# uControl_v1.net
KiCad netlist of a schematic drawn in EAGLE
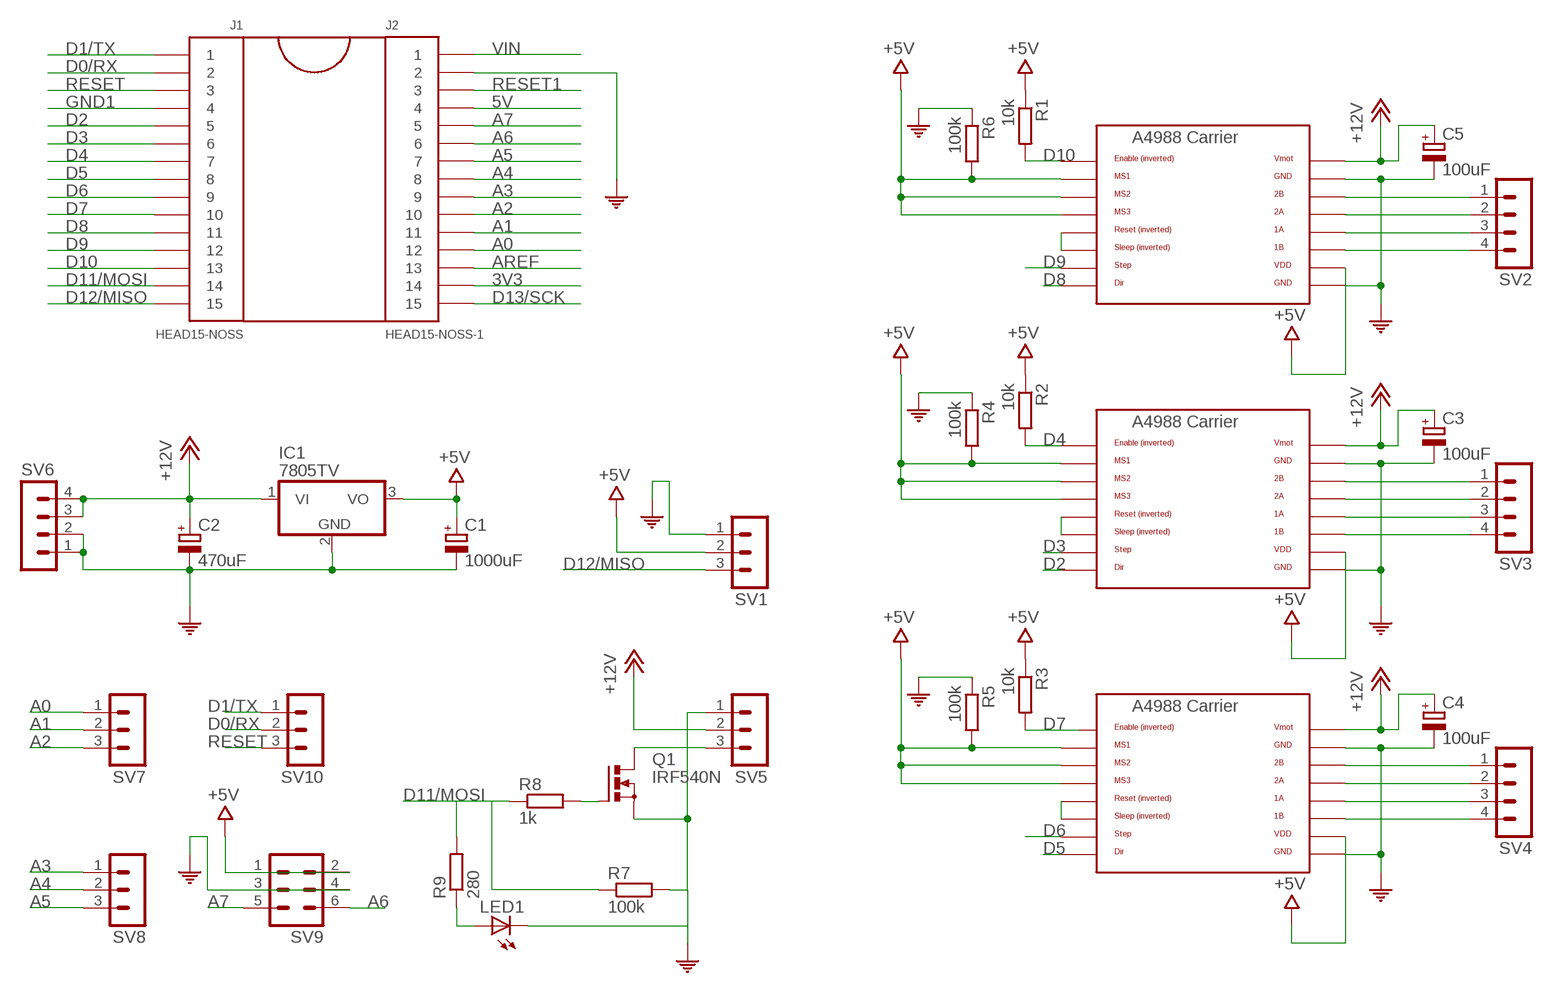
[diagram p0: schematic, sheet 1]

(export (version "E")
  (design (tool "Eeschema 10.0.6"))
  (components
    (comp (ref "C1")
      (value "1000uF")
      (footprint "eagle-import:TAP5-70")
      (libsource (lib "eagle-import") (part "CPOL-EUTAP5-70"))
    )
    (comp (ref "C2")
      (value "470uF")
      (footprint "eagle-import:TAP5-70")
      (libsource (lib "eagle-import") (part "CPOL-EUTAP5-70"))
    )
    (comp (ref "C3")
      (value "100uF")
      (footprint "eagle-import:TAP5-70")
      (libsource (lib "eagle-import") (part "CPOL-EUTAP5-70"))
    )
    (comp (ref "C4")
      (value "100uF")
      (footprint "eagle-import:TAP5-70")
      (libsource (lib "eagle-import") (part "CPOL-EUTAP5-70"))
    )
    (comp (ref "C5")
      (value "100uF")
      (footprint "eagle-import:TAP5-70")
      (libsource (lib "eagle-import") (part "CPOL-EUTAP5-70"))
    )
    (comp (ref "IC1")
      (value "7805TV")
      (footprint "eagle-import:TO220V")
      (libsource (lib "eagle-import") (part "78TV05"))
    )
    (comp (ref "J1")
      (value "HEAD15-NOSS")
      (footprint "eagle-import:HEAD15-NOSS")
      (libsource (lib "eagle-import") (part "HEAD15-NOSS"))
    )
    (comp (ref "J2")
      (value "HEAD15-NOSS-1")
      (footprint "eagle-import:HEAD15-NOSS-1")
      (libsource (lib "eagle-import") (part "HEAD15-NOSS-1"))
    )
    (comp (ref "LED1")
      (value "LED3MM")
      (footprint "eagle-import:LED3MM")
      (libsource (lib "eagle-import") (part "LED3MM"))
    )
    (comp (ref "Q1")
      (value "IRF540N")
      (footprint "eagle-import:TO220BV")
      (libsource (lib "eagle-import") (part "PMOSFET_NTO220BV"))
    )
    (comp (ref "R1")
      (value "10k")
      (footprint "eagle-import:0207_10")
      (libsource (lib "eagle-import") (part "R-EU_0207/10"))
    )
    (comp (ref "R2")
      (value "10k")
      (footprint "eagle-import:0207_10")
      (libsource (lib "eagle-import") (part "R-EU_0207/10"))
    )
    (comp (ref "R3")
      (value "10k")
      (footprint "eagle-import:0207_10")
      (libsource (lib "eagle-import") (part "R-EU_0207/10"))
    )
    (comp (ref "R4")
      (value "100k")
      (footprint "eagle-import:0207_10")
      (libsource (lib "eagle-import") (part "R-EU_0207/10"))
    )
    (comp (ref "R5")
      (value "100k")
      (footprint "eagle-import:0207_10")
      (libsource (lib "eagle-import") (part "R-EU_0207/10"))
    )
    (comp (ref "R6")
      (value "100k")
      (footprint "eagle-import:0207_10")
      (libsource (lib "eagle-import") (part "R-EU_0207/10"))
    )
    (comp (ref "R7")
      (value "100k")
      (footprint "eagle-import:0207_10")
      (libsource (lib "eagle-import") (part "R-EU_0207/10"))
    )
    (comp (ref "R8")
      (value "1k")
      (footprint "eagle-import:0207_10")
      (libsource (lib "eagle-import") (part "R-EU_0207/10"))
    )
    (comp (ref "R9")
      (value "280")
      (footprint "eagle-import:0207_10")
      (libsource (lib "eagle-import") (part "R-EU_0207/10"))
    )
    (comp (ref "SV1")
      (value "MA03-1")
      (footprint "eagle-import:MA03-1")
      (libsource (lib "eagle-import") (part "MA03-1"))
    )
    (comp (ref "SV2")
      (value "MA04-1")
      (footprint "eagle-import:MA04-1")
      (libsource (lib "eagle-import") (part "MA04-1"))
    )
    (comp (ref "SV3")
      (value "MA04-1")
      (footprint "eagle-import:MA04-1")
      (libsource (lib "eagle-import") (part "MA04-1"))
    )
    (comp (ref "SV4")
      (value "MA04-1")
      (footprint "eagle-import:MA04-1")
      (libsource (lib "eagle-import") (part "MA04-1"))
    )
    (comp (ref "SV5")
      (value "MA03-1")
      (footprint "eagle-import:MA03-1")
      (libsource (lib "eagle-import") (part "MA03-1"))
    )
    (comp (ref "SV6")
      (value "MA04-1")
      (footprint "eagle-import:MA04-1")
      (libsource (lib "eagle-import") (part "MA04-1"))
    )
    (comp (ref "SV7")
      (value "MA03-1")
      (footprint "eagle-import:MA03-1")
      (libsource (lib "eagle-import") (part "MA03-1"))
    )
    (comp (ref "SV8")
      (value "MA03-1")
      (footprint "eagle-import:MA03-1")
      (libsource (lib "eagle-import") (part "MA03-1"))
    )
    (comp (ref "SV9")
      (value "MA03-2")
      (footprint "eagle-import:MA03-2")
      (libsource (lib "eagle-import") (part "MA03-2"))
    )
    (comp (ref "SV10")
      (value "MA03-1")
      (footprint "eagle-import:MA03-1")
      (libsource (lib "eagle-import") (part "MA03-1"))
    )
    (comp (ref "U$3")
      (value "POLOLU_A4983CARRIER")
      (footprint "eagle-import:A4988BREAKOUT")
      (libsource (lib "eagle-import") (part "POLOLU_A4983CARRIER"))
    )
    (comp (ref "U$4")
      (value "A4988BREAKOUT")
      (footprint "eagle-import:A4988BREAKOUT")
      (libsource (lib "eagle-import") (part "A4988BREAKOUT"))
    )
    (comp (ref "U$5")
      (value "A4988BREAKOUT")
      (footprint "eagle-import:A4988BREAKOUT")
      (libsource (lib "eagle-import") (part "A4988BREAKOUT"))
    )
  )
  (nets
    (net (code "1") (name "+5V") (class "Default")
      (node (ref "C1") (pin "+") (pinfunction "+_+") (pintype "passive"))
      (node (ref "IC1") (pin "3") (pinfunction "VO_3") (pintype "passive"))
      (node (ref "R1") (pin "1") (pinfunction "1_1") (pintype "passive"))
      (node (ref "R2") (pin "1") (pinfunction "1_1") (pintype "passive"))
      (node (ref "R3") (pin "1") (pinfunction "1_1") (pintype "passive"))
      (node (ref "R4") (pin "2") (pinfunction "2_2") (pintype "passive"))
      (node (ref "R5") (pin "2") (pinfunction "2_2") (pintype "passive"))
      (node (ref "R6") (pin "2") (pinfunction "2_2") (pintype "passive"))
      (node (ref "SV1") (pin "2") (pinfunction "2_2") (pintype "passive"))
      (node (ref "SV9") (pin "1") (pinfunction "1_1") (pintype "passive"))
      (node (ref "SV9") (pin "2") (pinfunction "2_2") (pintype "passive"))
      (node (ref "U$3") (pin "MS1") (pinfunction "MS1_MS1") (pintype "input"))
      (node (ref "U$3") (pin "MS2") (pinfunction "MS2_MS2") (pintype "input"))
      (node (ref "U$3") (pin "MS3") (pinfunction "MS3_MS3") (pintype "input"))
      (node (ref "U$3") (pin "VDD") (pinfunction "VDD_VDD") (pintype "power_in"))
      (node (ref "U$4") (pin "MS1") (pinfunction "MS1_MS1") (pintype "input"))
      (node (ref "U$4") (pin "MS2") (pinfunction "MS2_MS2") (pintype "input"))
      (node (ref "U$4") (pin "MS3") (pinfunction "MS3_MS3") (pintype "input"))
      (node (ref "U$4") (pin "VDD") (pinfunction "VDD_VDD") (pintype "power_in"))
      (node (ref "U$5") (pin "MS1") (pinfunction "MS1_MS1") (pintype "input"))
      (node (ref "U$5") (pin "MS2") (pinfunction "MS2_MS2") (pintype "input"))
      (node (ref "U$5") (pin "MS3") (pinfunction "MS3_MS3") (pintype "input"))
      (node (ref "U$5") (pin "VDD") (pinfunction "VDD_VDD") (pintype "power_in"))
    )
    (net (code "2") (name "+12V") (class "Default")
      (node (ref "C2") (pin "+") (pinfunction "+_+") (pintype "passive"))
      (node (ref "C3") (pin "+") (pinfunction "+_+") (pintype "passive"))
      (node (ref "C4") (pin "+") (pinfunction "+_+") (pintype "passive"))
      (node (ref "C5") (pin "+") (pinfunction "+_+") (pintype "passive"))
      (node (ref "IC1") (pin "1") (pinfunction "VI_1") (pintype "input"))
      (node (ref "SV5") (pin "2") (pinfunction "2_2") (pintype "passive"))
      (node (ref "SV6") (pin "3") (pinfunction "3_3") (pintype "passive"))
      (node (ref "SV6") (pin "4") (pinfunction "4_4") (pintype "passive"))
      (node (ref "U$3") (pin "VMOT") (pinfunction "VMOT_VMOT") (pintype "power_in"))
      (node (ref "U$4") (pin "VMOT") (pinfunction "VMOT_VMOT") (pintype "power_in"))
      (node (ref "U$5") (pin "VMOT") (pinfunction "VMOT_VMOT") (pintype "power_in"))
    )
    (net (code "3") (name "/3V3") (class "Default")
      (node (ref "J2") (pin "14") (pinfunction "14_14") (pintype "passive"))
    )
    (net (code "4") (name "/5V") (class "Default")
      (node (ref "J2") (pin "4") (pinfunction "4_4") (pintype "passive"))
    )
    (net (code "5") (name "/A0") (class "Default")
      (node (ref "J2") (pin "12") (pinfunction "12_12") (pintype "passive"))
      (node (ref "SV7") (pin "1") (pinfunction "1_1") (pintype "passive"))
    )
    (net (code "6") (name "/A1") (class "Default")
      (node (ref "J2") (pin "11") (pinfunction "11_11") (pintype "passive"))
      (node (ref "SV7") (pin "2") (pinfunction "2_2") (pintype "passive"))
    )
    (net (code "7") (name "/A2") (class "Default")
      (node (ref "J2") (pin "10") (pinfunction "10_10") (pintype "passive"))
      (node (ref "SV7") (pin "3") (pinfunction "3_3") (pintype "passive"))
    )
    (net (code "8") (name "/A3") (class "Default")
      (node (ref "J2") (pin "9") (pinfunction "9_9") (pintype "passive"))
      (node (ref "SV8") (pin "1") (pinfunction "1_1") (pintype "passive"))
    )
    (net (code "9") (name "/A4") (class "Default")
      (node (ref "J2") (pin "8") (pinfunction "8_8") (pintype "passive"))
      (node (ref "SV8") (pin "2") (pinfunction "2_2") (pintype "passive"))
    )
    (net (code "10") (name "/A5") (class "Default")
      (node (ref "J2") (pin "7") (pinfunction "7_7") (pintype "passive"))
      (node (ref "SV8") (pin "3") (pinfunction "3_3") (pintype "passive"))
    )
    (net (code "11") (name "/A6") (class "Default")
      (node (ref "J2") (pin "6") (pinfunction "6_6") (pintype "passive"))
      (node (ref "SV9") (pin "6") (pinfunction "6_6") (pintype "passive"))
    )
    (net (code "12") (name "/A7") (class "Default")
      (node (ref "J2") (pin "5") (pinfunction "5_5") (pintype "passive"))
      (node (ref "SV9") (pin "5") (pinfunction "5_5") (pintype "passive"))
    )
    (net (code "13") (name "/AREF") (class "Default")
      (node (ref "J2") (pin "13") (pinfunction "13_13") (pintype "passive"))
    )
    (net (code "14") (name "/D0{slash}RX") (class "Default")
      (node (ref "J1") (pin "2") (pinfunction "2_2") (pintype "passive"))
      (node (ref "SV10") (pin "2") (pinfunction "2_2") (pintype "passive"))
    )
    (net (code "15") (name "/D1{slash}TX") (class "Default")
      (node (ref "J1") (pin "1") (pinfunction "1_1") (pintype "passive"))
      (node (ref "SV10") (pin "1") (pinfunction "1_1") (pintype "passive"))
    )
    (net (code "16") (name "/D2") (class "Default")
      (node (ref "J1") (pin "5") (pinfunction "5_5") (pintype "passive"))
      (node (ref "U$5") (pin "DIR") (pinfunction "DIR_DIR") (pintype "input"))
    )
    (net (code "17") (name "/D3") (class "Default")
      (node (ref "J1") (pin "6") (pinfunction "6_6") (pintype "passive"))
      (node (ref "U$5") (pin "STEP") (pinfunction "STEP_STEP") (pintype "input"))
    )
    (net (code "18") (name "/D4") (class "Default")
      (node (ref "J1") (pin "7") (pinfunction "7_7") (pintype "passive"))
      (node (ref "R2") (pin "2") (pinfunction "2_2") (pintype "passive"))
      (node (ref "U$5") (pin "EN") (pinfunction "EN_EN") (pintype "input"))
    )
    (net (code "19") (name "/D5") (class "Default")
      (node (ref "J1") (pin "8") (pinfunction "8_8") (pintype "passive"))
      (node (ref "U$4") (pin "DIR") (pinfunction "DIR_DIR") (pintype "input"))
    )
    (net (code "20") (name "/D6") (class "Default")
      (node (ref "J1") (pin "9") (pinfunction "9_9") (pintype "passive"))
      (node (ref "U$4") (pin "STEP") (pinfunction "STEP_STEP") (pintype "input"))
    )
    (net (code "21") (name "/D7") (class "Default")
      (node (ref "J1") (pin "10") (pinfunction "10_10") (pintype "passive"))
      (node (ref "R3") (pin "2") (pinfunction "2_2") (pintype "passive"))
      (node (ref "U$4") (pin "EN") (pinfunction "EN_EN") (pintype "input"))
    )
    (net (code "22") (name "/D8") (class "Default")
      (node (ref "J1") (pin "11") (pinfunction "11_11") (pintype "passive"))
      (node (ref "U$3") (pin "DIR") (pinfunction "DIR_DIR") (pintype "input"))
    )
    (net (code "23") (name "/D9") (class "Default")
      (node (ref "J1") (pin "12") (pinfunction "12_12") (pintype "passive"))
      (node (ref "U$3") (pin "STEP") (pinfunction "STEP_STEP") (pintype "input"))
    )
    (net (code "24") (name "/D10") (class "Default")
      (node (ref "J1") (pin "13") (pinfunction "13_13") (pintype "passive"))
      (node (ref "R1") (pin "2") (pinfunction "2_2") (pintype "passive"))
      (node (ref "U$3") (pin "EN") (pinfunction "EN_EN") (pintype "input"))
    )
    (net (code "25") (name "/D11{slash}MOSI") (class "Default")
      (node (ref "J1") (pin "14") (pinfunction "14_14") (pintype "passive"))
      (node (ref "R7") (pin "1") (pinfunction "1_1") (pintype "passive"))
      (node (ref "R8") (pin "1") (pinfunction "1_1") (pintype "passive"))
      (node (ref "R9") (pin "2") (pinfunction "2_2") (pintype "passive"))
    )
    (net (code "26") (name "/D12{slash}MISO") (class "Default")
      (node (ref "J1") (pin "15") (pinfunction "15_15") (pintype "passive"))
      (node (ref "SV1") (pin "3") (pinfunction "3_3") (pintype "passive"))
    )
    (net (code "27") (name "/D13{slash}SCK") (class "Default")
      (node (ref "J2") (pin "15") (pinfunction "15_15") (pintype "passive"))
    )
    (net (code "28") (name "/GND1") (class "Default")
      (node (ref "J1") (pin "4") (pinfunction "4_4") (pintype "passive"))
    )
    (net (code "29") (name "/RESET") (class "Default")
      (node (ref "J1") (pin "3") (pinfunction "3_3") (pintype "passive"))
      (node (ref "SV10") (pin "3") (pinfunction "3_3") (pintype "passive"))
    )
    (net (code "30") (name "/RESET1") (class "Default")
      (node (ref "J2") (pin "3") (pinfunction "3_3") (pintype "passive"))
    )
    (net (code "31") (name "/VIN") (class "Default")
      (node (ref "J2") (pin "1") (pinfunction "1_1") (pintype "passive"))
    )
    (net (code "32") (name "COM") (class "Default")
      (node (ref "C1") (pin "-") (pinfunction "-_-") (pintype "passive"))
      (node (ref "C2") (pin "-") (pinfunction "-_-") (pintype "passive"))
      (node (ref "C3") (pin "-") (pinfunction "-_-") (pintype "passive"))
      (node (ref "C4") (pin "-") (pinfunction "-_-") (pintype "passive"))
      (node (ref "C5") (pin "-") (pinfunction "-_-") (pintype "passive"))
      (node (ref "IC1") (pin "2") (pinfunction "GND_2") (pintype "passive"))
      (node (ref "J2") (pin "2") (pinfunction "2_2") (pintype "passive"))
      (node (ref "LED1") (pin "K") (pinfunction "C_K") (pintype "passive"))
      (node (ref "Q1") (pin "S") (pinfunction "S_S") (pintype "passive"))
      (node (ref "R4") (pin "1") (pinfunction "1_1") (pintype "passive"))
      (node (ref "R5") (pin "1") (pinfunction "1_1") (pintype "passive"))
      (node (ref "R6") (pin "1") (pinfunction "1_1") (pintype "passive"))
      (node (ref "R7") (pin "2") (pinfunction "2_2") (pintype "passive"))
      (node (ref "SV1") (pin "1") (pinfunction "1_1") (pintype "passive"))
      (node (ref "SV5") (pin "1") (pinfunction "1_1") (pintype "passive"))
      (node (ref "SV6") (pin "1") (pinfunction "1_1") (pintype "passive"))
      (node (ref "SV6") (pin "2") (pinfunction "2_2") (pintype "passive"))
      (node (ref "SV9") (pin "3") (pinfunction "3_3") (pintype "passive"))
      (node (ref "SV9") (pin "4") (pinfunction "4_4") (pintype "passive"))
      (node (ref "U$3") (pin "GND") (pinfunction "GND_GND") (pintype "power_in"))
      (node (ref "U$3") (pin "GND@0") (pinfunction "GND_GND@0") (pintype "power_in"))
      (node (ref "U$4") (pin "GND") (pinfunction "GND_GND") (pintype "power_in"))
      (node (ref "U$4") (pin "GND@0") (pinfunction "GND_GND@0") (pintype "power_in"))
      (node (ref "U$5") (pin "GND") (pinfunction "GND_GND") (pintype "power_in"))
      (node (ref "U$5") (pin "GND@0") (pinfunction "GND_GND@0") (pintype "power_in"))
    )
    (net (code "33") (name "Net-(LED1-PadA)") (class "Default")
      (node (ref "LED1") (pin "A") (pinfunction "A_A") (pintype "passive"))
      (node (ref "R9") (pin "1") (pinfunction "1_1") (pintype "passive"))
    )
    (net (code "34") (name "Net-(Q1-PadD)") (class "Default")
      (node (ref "Q1") (pin "D") (pinfunction "D_D") (pintype "passive"))
      (node (ref "SV5") (pin "3") (pinfunction "3_3") (pintype "passive"))
    )
    (net (code "35") (name "Net-(Q1-PadG)") (class "Default")
      (node (ref "Q1") (pin "G") (pinfunction "G_G") (pintype "passive"))
      (node (ref "R8") (pin "2") (pinfunction "2_2") (pintype "passive"))
    )
    (net (code "36") (name "Net-(SV2-Pad1)") (class "Default")
      (node (ref "SV2") (pin "1") (pinfunction "1_1") (pintype "passive"))
      (node (ref "U$3") (pin "2B") (pinfunction "2B_2B") (pintype "output"))
    )
    (net (code "37") (name "Net-(SV2-Pad2)") (class "Default")
      (node (ref "SV2") (pin "2") (pinfunction "2_2") (pintype "passive"))
      (node (ref "U$3") (pin "2A") (pinfunction "2A_2A") (pintype "output"))
    )
    (net (code "38") (name "Net-(SV2-Pad3)") (class "Default")
      (node (ref "SV2") (pin "3") (pinfunction "3_3") (pintype "passive"))
      (node (ref "U$3") (pin "1A") (pinfunction "1A_1A") (pintype "output"))
    )
    (net (code "39") (name "Net-(SV2-Pad4)") (class "Default")
      (node (ref "SV2") (pin "4") (pinfunction "4_4") (pintype "passive"))
      (node (ref "U$3") (pin "1B") (pinfunction "1B_1B") (pintype "output"))
    )
    (net (code "40") (name "Net-(SV3-Pad1)") (class "Default")
      (node (ref "SV3") (pin "1") (pinfunction "1_1") (pintype "passive"))
      (node (ref "U$5") (pin "2B") (pinfunction "2B_2B") (pintype "output"))
    )
    (net (code "41") (name "Net-(SV3-Pad2)") (class "Default")
      (node (ref "SV3") (pin "2") (pinfunction "2_2") (pintype "passive"))
      (node (ref "U$5") (pin "2A") (pinfunction "2A_2A") (pintype "output"))
    )
    (net (code "42") (name "Net-(SV3-Pad3)") (class "Default")
      (node (ref "SV3") (pin "3") (pinfunction "3_3") (pintype "passive"))
      (node (ref "U$5") (pin "1A") (pinfunction "1A_1A") (pintype "output"))
    )
    (net (code "43") (name "Net-(SV3-Pad4)") (class "Default")
      (node (ref "SV3") (pin "4") (pinfunction "4_4") (pintype "passive"))
      (node (ref "U$5") (pin "1B") (pinfunction "1B_1B") (pintype "output"))
    )
    (net (code "44") (name "Net-(SV4-Pad1)") (class "Default")
      (node (ref "SV4") (pin "1") (pinfunction "1_1") (pintype "passive"))
      (node (ref "U$4") (pin "2B") (pinfunction "2B_2B") (pintype "output"))
    )
    (net (code "45") (name "Net-(SV4-Pad2)") (class "Default")
      (node (ref "SV4") (pin "2") (pinfunction "2_2") (pintype "passive"))
      (node (ref "U$4") (pin "2A") (pinfunction "2A_2A") (pintype "output"))
    )
    (net (code "46") (name "Net-(SV4-Pad3)") (class "Default")
      (node (ref "SV4") (pin "3") (pinfunction "3_3") (pintype "passive"))
      (node (ref "U$4") (pin "1A") (pinfunction "1A_1A") (pintype "output"))
    )
    (net (code "47") (name "Net-(SV4-Pad4)") (class "Default")
      (node (ref "SV4") (pin "4") (pinfunction "4_4") (pintype "passive"))
      (node (ref "U$4") (pin "1B") (pinfunction "1B_1B") (pintype "output"))
    )
    (net (code "48") (name "Net-(U$3-SLEEP)") (class "Default")
      (node (ref "U$3") (pin "RST") (pinfunction "RST_RST") (pintype "input"))
      (node (ref "U$3") (pin "SLP") (pinfunction "SLEEP_SLP") (pintype "input"))
    )
    (net (code "49") (name "Net-(U$4-SLEEP)") (class "Default")
      (node (ref "U$4") (pin "RST") (pinfunction "RST_RST") (pintype "input"))
      (node (ref "U$4") (pin "SLP") (pinfunction "SLEEP_SLP") (pintype "input"))
    )
    (net (code "50") (name "Net-(U$5-SLEEP)") (class "Default")
      (node (ref "U$5") (pin "RST") (pinfunction "RST_RST") (pintype "input"))
      (node (ref "U$5") (pin "SLP") (pinfunction "SLEEP_SLP") (pintype "input"))
    )
  )
)
